# Power_Subsystem.net
KiCad netlist of a schematic drawn in Altium Designer
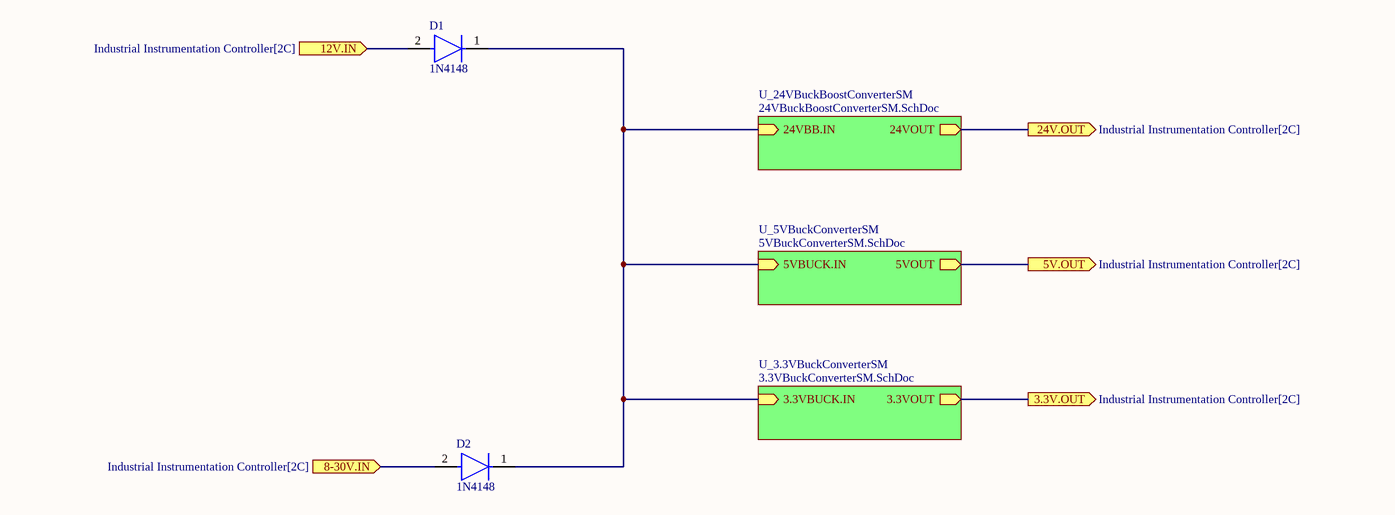
[diagram p0: Power Subsystem.SchDoc]

(export (version "E")
  (design (tool "Eeschema 10.0.6"))
  (components
    (comp (ref "D1")
      (value "1N4148")
      (footprint "FP-017AG-MFG")
      (description "DIODE GEN PURP 100V 200MA DO35")
      (fields (field (name "VOLTAGE") "100V"))
      (libsource (lib "Altium Content Vault") (part "d7152d700b627762746794eb795d46e"))
    )
    (comp (ref "D2")
      (value "1N4148")
      (footprint "FP-017AG-MFG")
      (description "DIODE GEN PURP 100V 200MA DO35")
      (fields (field (name "VOLTAGE") "100V"))
      (libsource (lib "Altium Content Vault") (part "d7152d700b627762746794eb795d46e"))
    )
  )
  (nets
    (net (code "3") (name "/8-30V.IN") (class "Default")
      (node (ref "D2") (pin "2") (pinfunction "A_2") (pintype "passive"))
    )
    (net (code "4") (name "/12V.IN") (class "Default")
      (node (ref "D1") (pin "2") (pinfunction "A_2") (pintype "passive"))
    )
    (net (code "6") (name "/24VBB.IN") (class "Default")
      (node (ref "D1") (pin "1") (pinfunction "C_1") (pintype "passive"))
      (node (ref "D2") (pin "1") (pinfunction "C_1") (pintype "passive"))
    )
  )
)
